# breakout-4x-step-down.net
KiCad netlist of a schematic drawn in EAGLE
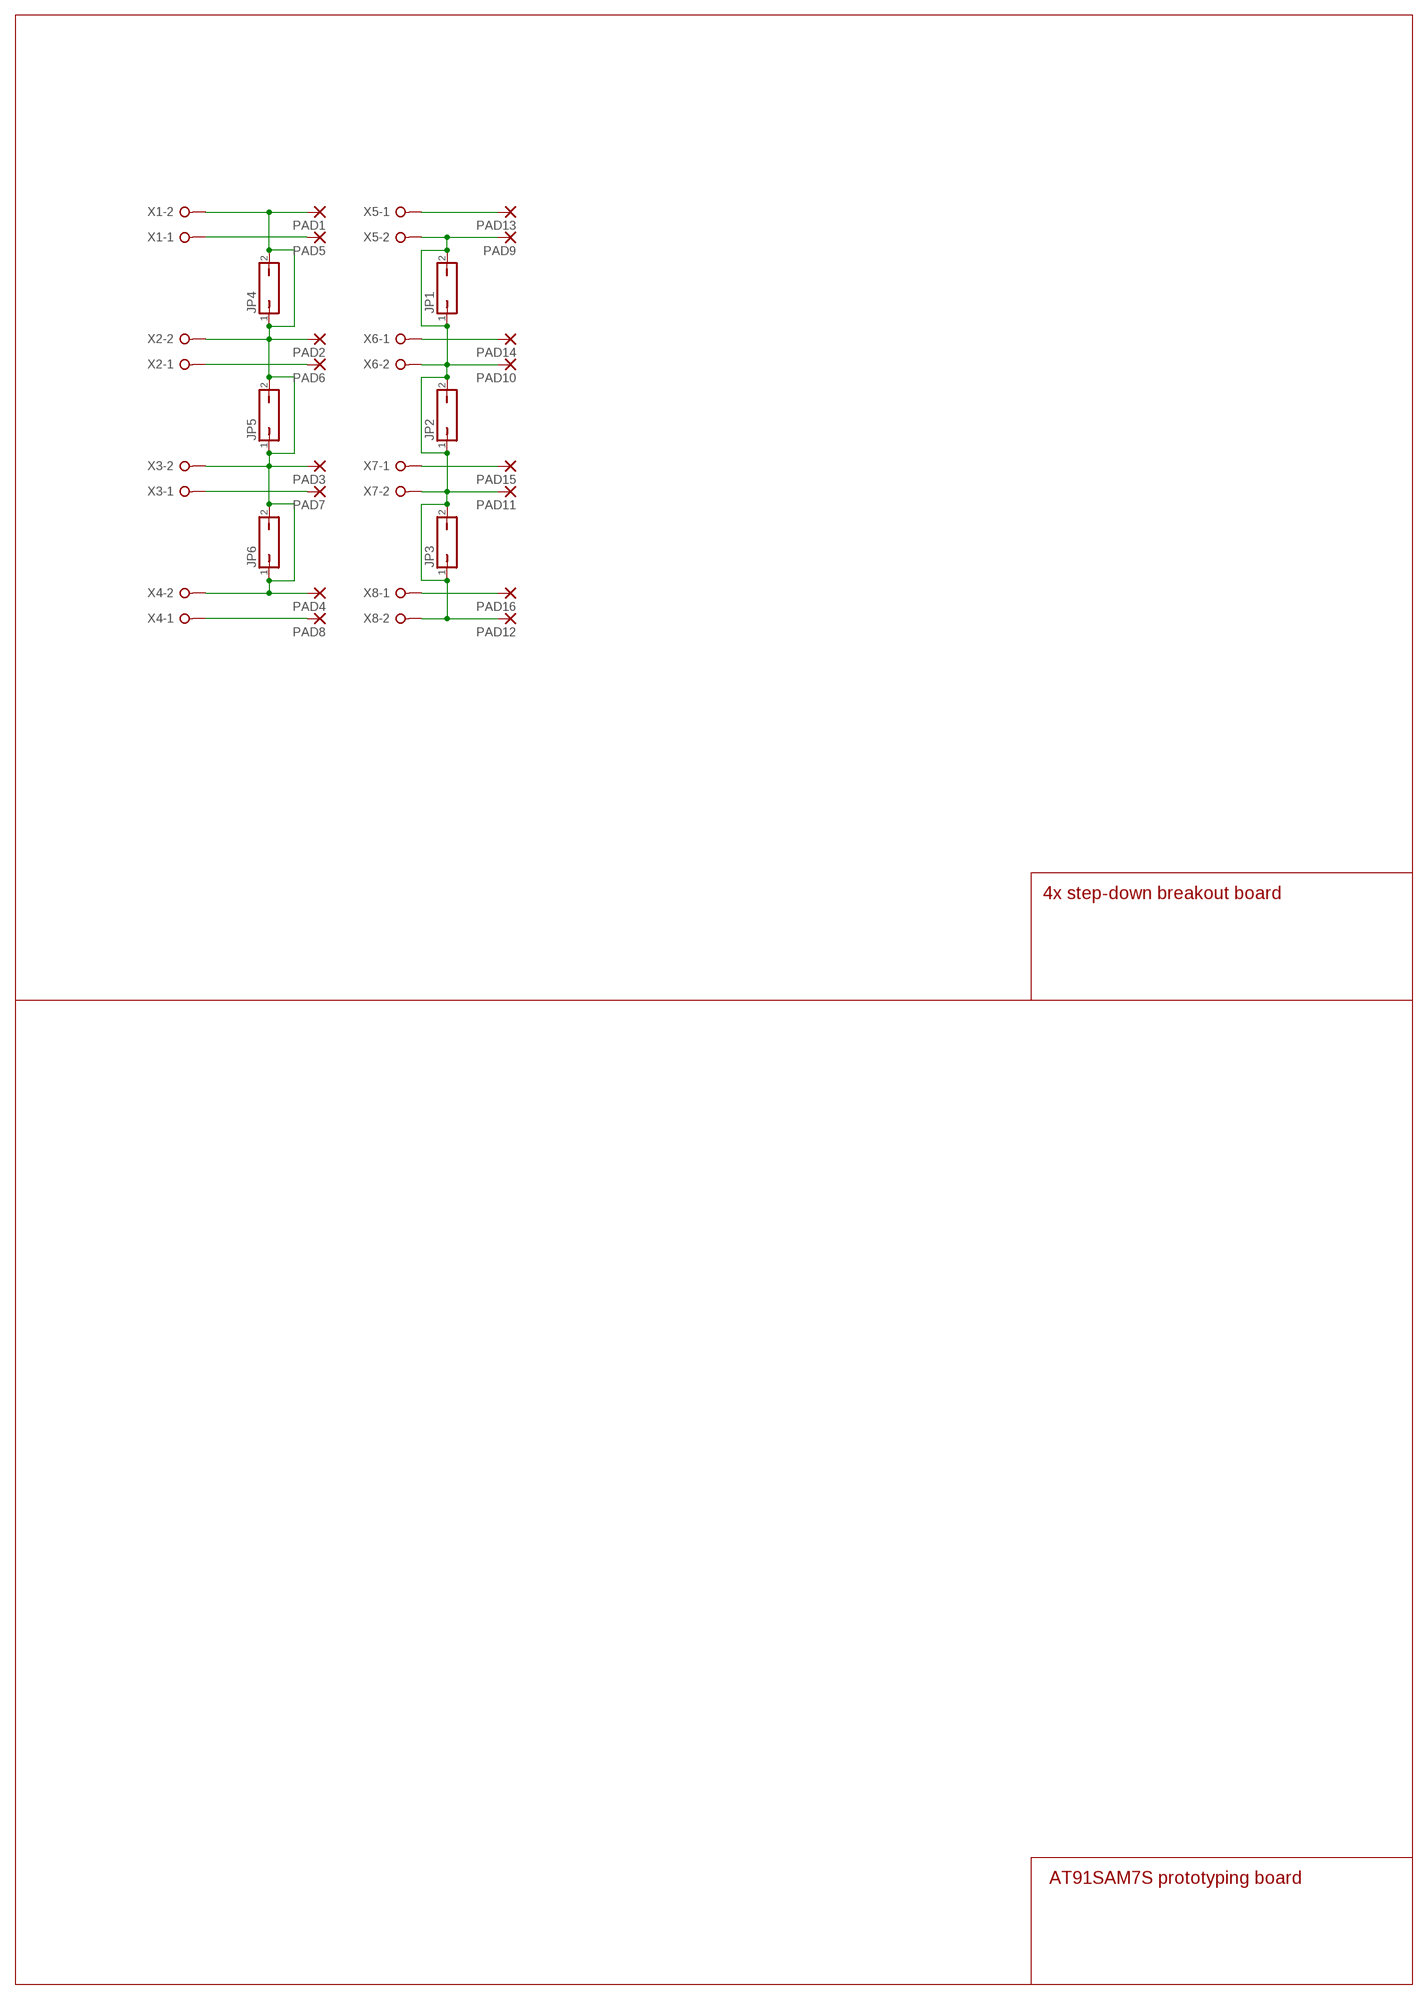
[diagram p0: schematic, sheet 1]

(export (version "E")
  (design (tool "Eeschema 10.0.6"))
  (components
    (comp (ref "JP1")
      (value "JP1Q")
      (footprint "eagle-import:JP1")
      (libsource (lib "eagle-import") (part "JP1Q"))
    )
    (comp (ref "JP2")
      (value "JP1Q")
      (footprint "eagle-import:JP1")
      (libsource (lib "eagle-import") (part "JP1Q"))
    )
    (comp (ref "JP3")
      (value "JP1Q")
      (footprint "eagle-import:JP1")
      (libsource (lib "eagle-import") (part "JP1Q"))
    )
    (comp (ref "JP4")
      (value "JP1Q")
      (footprint "eagle-import:JP1")
      (libsource (lib "eagle-import") (part "JP1Q"))
    )
    (comp (ref "JP5")
      (value "JP1Q")
      (footprint "eagle-import:JP1")
      (libsource (lib "eagle-import") (part "JP1Q"))
    )
    (comp (ref "JP6")
      (value "JP1Q")
      (footprint "eagle-import:JP1")
      (libsource (lib "eagle-import") (part "JP1Q"))
    )
    (comp (ref "PAD1")
      (value "1,6/0,8")
      (footprint "eagle-import:1,6_0,8")
      (libsource (lib "eagle-import") (part "1,6/0,8"))
    )
    (comp (ref "PAD2")
      (value "1,6/0,8")
      (footprint "eagle-import:1,6_0,8")
      (libsource (lib "eagle-import") (part "1,6/0,8"))
    )
    (comp (ref "PAD3")
      (value "1,6/0,8")
      (footprint "eagle-import:1,6_0,8")
      (libsource (lib "eagle-import") (part "1,6/0,8"))
    )
    (comp (ref "PAD4")
      (value "1,6/0,8")
      (footprint "eagle-import:1,6_0,8")
      (libsource (lib "eagle-import") (part "1,6/0,8"))
    )
    (comp (ref "PAD5")
      (value "1,6/0,8")
      (footprint "eagle-import:1,6_0,8")
      (libsource (lib "eagle-import") (part "1,6/0,8"))
    )
    (comp (ref "PAD6")
      (value "1,6/0,8")
      (footprint "eagle-import:1,6_0,8")
      (libsource (lib "eagle-import") (part "1,6/0,8"))
    )
    (comp (ref "PAD7")
      (value "1,6/0,8")
      (footprint "eagle-import:1,6_0,8")
      (libsource (lib "eagle-import") (part "1,6/0,8"))
    )
    (comp (ref "PAD8")
      (value "1,6/0,8")
      (footprint "eagle-import:1,6_0,8")
      (libsource (lib "eagle-import") (part "1,6/0,8"))
    )
    (comp (ref "PAD9")
      (value "1,6/0,8")
      (footprint "eagle-import:1,6_0,8")
      (libsource (lib "eagle-import") (part "1,6/0,8"))
    )
    (comp (ref "PAD10")
      (value "1,6/0,8")
      (footprint "eagle-import:1,6_0,8")
      (libsource (lib "eagle-import") (part "1,6/0,8"))
    )
    (comp (ref "PAD11")
      (value "1,6/0,8")
      (footprint "eagle-import:1,6_0,8")
      (libsource (lib "eagle-import") (part "1,6/0,8"))
    )
    (comp (ref "PAD12")
      (value "1,6/0,8")
      (footprint "eagle-import:1,6_0,8")
      (libsource (lib "eagle-import") (part "1,6/0,8"))
    )
    (comp (ref "PAD13")
      (value "1,6/0,8")
      (footprint "eagle-import:1,6_0,8")
      (libsource (lib "eagle-import") (part "1,6/0,8"))
    )
    (comp (ref "PAD14")
      (value "1,6/0,8")
      (footprint "eagle-import:1,6_0,8")
      (libsource (lib "eagle-import") (part "1,6/0,8"))
    )
    (comp (ref "PAD15")
      (value "1,6/0,8")
      (footprint "eagle-import:1,6_0,8")
      (libsource (lib "eagle-import") (part "1,6/0,8"))
    )
    (comp (ref "PAD16")
      (value "1,6/0,8")
      (footprint "eagle-import:1,6_0,8")
      (libsource (lib "eagle-import") (part "1,6/0,8"))
    )
    (comp (ref "X1")
      (value "W237-02P")
      (footprint "eagle-import:W237-132")
      (libsource (lib "eagle-import") (part "W237-02P"))
    )
    (comp (ref "X2")
      (value "W237-02P")
      (footprint "eagle-import:W237-132")
      (libsource (lib "eagle-import") (part "W237-02P"))
    )
    (comp (ref "X3")
      (value "W237-02P")
      (footprint "eagle-import:W237-132")
      (libsource (lib "eagle-import") (part "W237-02P"))
    )
    (comp (ref "X4")
      (value "W237-02P")
      (footprint "eagle-import:W237-132")
      (libsource (lib "eagle-import") (part "W237-02P"))
    )
    (comp (ref "X5")
      (value "W237-02P")
      (footprint "eagle-import:W237-132")
      (libsource (lib "eagle-import") (part "W237-02P"))
    )
    (comp (ref "X6")
      (value "W237-02P")
      (footprint "eagle-import:W237-132")
      (libsource (lib "eagle-import") (part "W237-02P"))
    )
    (comp (ref "X7")
      (value "W237-02P")
      (footprint "eagle-import:W237-132")
      (libsource (lib "eagle-import") (part "W237-02P"))
    )
    (comp (ref "X8")
      (value "W237-02P")
      (footprint "eagle-import:W237-132")
      (libsource (lib "eagle-import") (part "W237-02P"))
    )
  )
  (nets
    (net (code "1") (name "Net-(PAD1-P)") (class "Default")
      (node (ref "JP4") (pin "1") (pinfunction "1_1") (pintype "passive"))
      (node (ref "JP4") (pin "2") (pinfunction "2_2") (pintype "passive"))
      (node (ref "JP5") (pin "1") (pinfunction "1_1") (pintype "passive"))
      (node (ref "JP5") (pin "2") (pinfunction "2_2") (pintype "passive"))
      (node (ref "JP6") (pin "1") (pinfunction "1_1") (pintype "passive"))
      (node (ref "JP6") (pin "2") (pinfunction "2_2") (pintype "passive"))
      (node (ref "PAD1") (pin "1") (pinfunction "P_1") (pintype "passive"))
      (node (ref "PAD2") (pin "1") (pinfunction "P_1") (pintype "passive"))
      (node (ref "PAD3") (pin "1") (pinfunction "P_1") (pintype "passive"))
      (node (ref "PAD4") (pin "1") (pinfunction "P_1") (pintype "passive"))
      (node (ref "X1") (pin "2") (pinfunction "KL_2") (pintype "passive"))
      (node (ref "X2") (pin "2") (pinfunction "KL_2") (pintype "passive"))
      (node (ref "X3") (pin "2") (pinfunction "KL_2") (pintype "passive"))
      (node (ref "X4") (pin "2") (pinfunction "KL_2") (pintype "passive"))
    )
    (net (code "2") (name "Net-(PAD5-P)") (class "Default")
      (node (ref "PAD5") (pin "1") (pinfunction "P_1") (pintype "passive"))
      (node (ref "X1") (pin "1") (pinfunction "KL_1") (pintype "passive"))
    )
    (net (code "3") (name "Net-(PAD6-P)") (class "Default")
      (node (ref "PAD6") (pin "1") (pinfunction "P_1") (pintype "passive"))
      (node (ref "X2") (pin "1") (pinfunction "KL_1") (pintype "passive"))
    )
    (net (code "4") (name "Net-(PAD7-P)") (class "Default")
      (node (ref "PAD7") (pin "1") (pinfunction "P_1") (pintype "passive"))
      (node (ref "X3") (pin "1") (pinfunction "KL_1") (pintype "passive"))
    )
    (net (code "5") (name "Net-(PAD8-P)") (class "Default")
      (node (ref "PAD8") (pin "1") (pinfunction "P_1") (pintype "passive"))
      (node (ref "X4") (pin "1") (pinfunction "KL_1") (pintype "passive"))
    )
    (net (code "6") (name "Net-(PAD10-P)") (class "Default")
      (node (ref "JP1") (pin "1") (pinfunction "1_1") (pintype "passive"))
      (node (ref "JP1") (pin "2") (pinfunction "2_2") (pintype "passive"))
      (node (ref "JP2") (pin "1") (pinfunction "1_1") (pintype "passive"))
      (node (ref "JP2") (pin "2") (pinfunction "2_2") (pintype "passive"))
      (node (ref "JP3") (pin "1") (pinfunction "1_1") (pintype "passive"))
      (node (ref "JP3") (pin "2") (pinfunction "2_2") (pintype "passive"))
      (node (ref "PAD10") (pin "1") (pinfunction "P_1") (pintype "passive"))
      (node (ref "PAD11") (pin "1") (pinfunction "P_1") (pintype "passive"))
      (node (ref "PAD12") (pin "1") (pinfunction "P_1") (pintype "passive"))
      (node (ref "PAD9") (pin "1") (pinfunction "P_1") (pintype "passive"))
      (node (ref "X5") (pin "2") (pinfunction "KL_2") (pintype "passive"))
      (node (ref "X6") (pin "2") (pinfunction "KL_2") (pintype "passive"))
      (node (ref "X7") (pin "2") (pinfunction "KL_2") (pintype "passive"))
      (node (ref "X8") (pin "2") (pinfunction "KL_2") (pintype "passive"))
    )
    (net (code "7") (name "Net-(PAD13-P)") (class "Default")
      (node (ref "PAD13") (pin "1") (pinfunction "P_1") (pintype "passive"))
      (node (ref "X5") (pin "1") (pinfunction "KL_1") (pintype "passive"))
    )
    (net (code "8") (name "Net-(PAD14-P)") (class "Default")
      (node (ref "PAD14") (pin "1") (pinfunction "P_1") (pintype "passive"))
      (node (ref "X6") (pin "1") (pinfunction "KL_1") (pintype "passive"))
    )
    (net (code "9") (name "Net-(PAD15-P)") (class "Default")
      (node (ref "PAD15") (pin "1") (pinfunction "P_1") (pintype "passive"))
      (node (ref "X7") (pin "1") (pinfunction "KL_1") (pintype "passive"))
    )
    (net (code "10") (name "Net-(PAD16-P)") (class "Default")
      (node (ref "PAD16") (pin "1") (pinfunction "P_1") (pintype "passive"))
      (node (ref "X8") (pin "1") (pinfunction "KL_1") (pintype "passive"))
    )
  )
)
